# Mosfet_switch_options_breakout_board.net
KiCad netlist of a schematic drawn in EAGLE
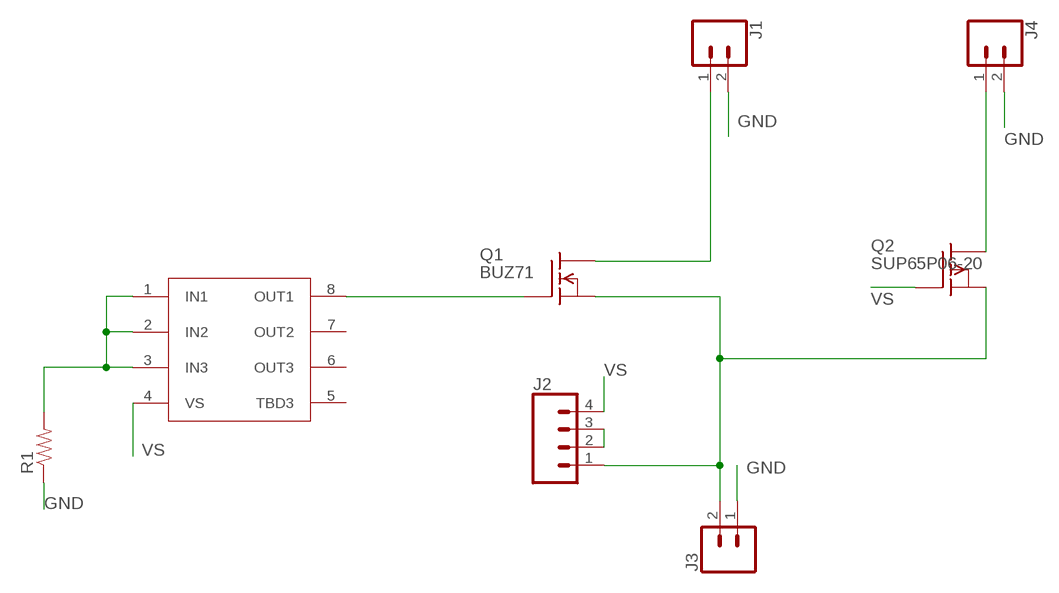
[diagram p0: schematic, sheet 1]

(export (version "E")
  (design (tool "Eeschema 10.0.6"))
  (components
    (comp (ref "J1")
      (value "CONN_02")
      (footprint "eagle-import:1X02")
      (libsource (lib "eagle-import") (part "CONN_02"))
    )
    (comp (ref "J2")
      (value "CONN_04")
      (footprint "eagle-import:1X04")
      (libsource (lib "eagle-import") (part "CONN_04"))
    )
    (comp (ref "J3")
      (value "CONN_02")
      (footprint "eagle-import:1X02")
      (libsource (lib "eagle-import") (part "CONN_02"))
    )
    (comp (ref "J4")
      (value "CONN_02")
      (footprint "eagle-import:1X02")
      (libsource (lib "eagle-import") (part "CONN_02"))
    )
    (comp (ref "Q1")
      (value "BUZ71")
      (footprint "eagle-import:TO220")
      (libsource (lib "eagle-import") (part "BUZ71"))
    )
    (comp (ref "Q2")
      (value "SUP65P06-20")
      (footprint "eagle-import:TO220")
      (libsource (lib "eagle-import") (part "SUP65P06-20"))
    )
    (comp (ref "R1")
      (value "RESISTOR0805")
      (footprint "eagle-import:0805")
      (libsource (lib "eagle-import") (part "RESISTOR0805"))
    )
    (comp (ref "U$1")
      (value "(TEMP)MOSFET_DRIVER")
      (footprint "eagle-import:TSSOP-8")
      (libsource (lib "eagle-import") (part "(TEMP)MOSFET_DRIVER"))
    )
  )
  (nets
    (net (code "1") (name "/GND") (class "Default")
      (node (ref "J1") (pin "2") (pinfunction "2_2") (pintype "passive"))
      (node (ref "J3") (pin "1") (pinfunction "1_1") (pintype "passive"))
      (node (ref "J4") (pin "2") (pinfunction "2_2") (pintype "passive"))
      (node (ref "R1") (pin "1") (pinfunction "1_1") (pintype "passive"))
    )
    (net (code "2") (name "/VS") (class "Default")
      (node (ref "J2") (pin "4") (pinfunction "4_4") (pintype "passive"))
      (node (ref "Q2") (pin "1") (pinfunction "G_1") (pintype "passive"))
      (node (ref "U$1") (pin "4") (pinfunction "VS_4") (pintype "bidirectional"))
    )
    (net (code "3") (name "Net-(J2-Pad2)") (class "Default")
      (node (ref "J2") (pin "2") (pinfunction "2_2") (pintype "passive"))
      (node (ref "J2") (pin "3") (pinfunction "3_3") (pintype "passive"))
    )
    (net (code "4") (name "Net-(Q1-D)") (class "Default")
      (node (ref "J1") (pin "1") (pinfunction "1_1") (pintype "passive"))
      (node (ref "Q1") (pin "2") (pinfunction "D_2") (pintype "passive"))
    )
    (net (code "5") (name "Net-(Q1-G)") (class "Default")
      (node (ref "Q1") (pin "1") (pinfunction "G_1") (pintype "passive"))
      (node (ref "U$1") (pin "8") (pinfunction "OUT1_8") (pintype "bidirectional"))
    )
    (net (code "6") (name "Net-(Q1-S)") (class "Default")
      (node (ref "J2") (pin "1") (pinfunction "1_1") (pintype "passive"))
      (node (ref "J3") (pin "2") (pinfunction "2_2") (pintype "passive"))
      (node (ref "Q1") (pin "3") (pinfunction "S_3") (pintype "passive"))
      (node (ref "Q2") (pin "3") (pinfunction "S_3") (pintype "passive"))
    )
    (net (code "7") (name "Net-(Q2-D)") (class "Default")
      (node (ref "J4") (pin "1") (pinfunction "1_1") (pintype "passive"))
      (node (ref "Q2") (pin "2") (pinfunction "D_2") (pintype "passive"))
    )
    (net (code "8") (name "Net-(U$1-IN1)") (class "Default")
      (node (ref "R1") (pin "2") (pinfunction "2_2") (pintype "passive"))
      (node (ref "U$1") (pin "1") (pinfunction "IN1_1") (pintype "bidirectional"))
      (node (ref "U$1") (pin "2") (pinfunction "IN2_2") (pintype "bidirectional"))
      (node (ref "U$1") (pin "3") (pinfunction "IN3_3") (pintype "bidirectional"))
    )
    (net (code "9") (name "unconnected-(U$1-OUT2-Pad7)") (class "Default")
      (node (ref "U$1") (pin "7") (pinfunction "OUT2_7") (pintype "bidirectional"))
    )
    (net (code "10") (name "unconnected-(U$1-OUT3-Pad6)") (class "Default")
      (node (ref "U$1") (pin "6") (pinfunction "OUT3_6") (pintype "bidirectional"))
    )
    (net (code "11") (name "unconnected-(U$1-TBD3-Pad5)") (class "Default")
      (node (ref "U$1") (pin "5") (pinfunction "TBD3_5") (pintype "bidirectional"))
    )
  )
)
